# FTDI_FT230X_Example.net
KiCad netlist of a schematic drawn in EAGLE
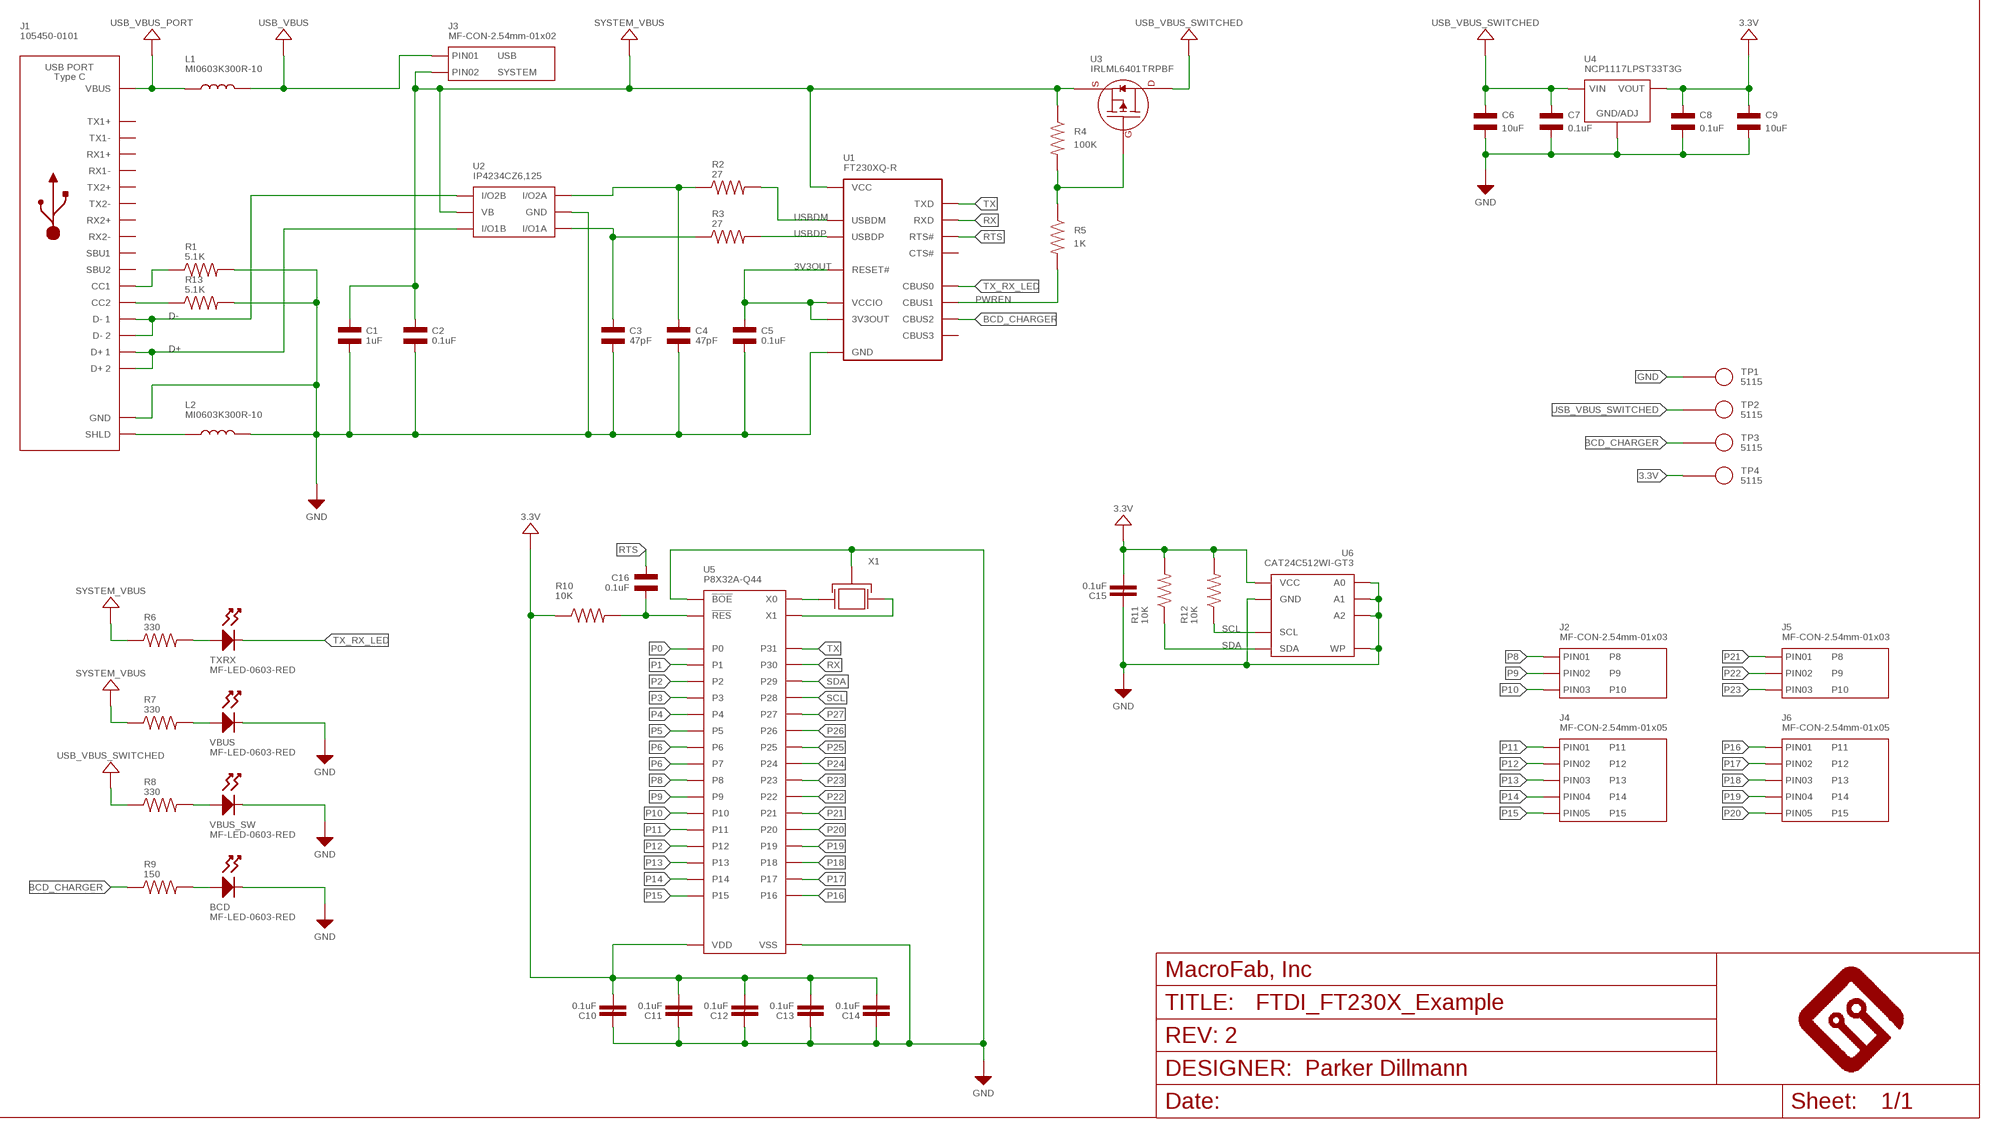
[diagram p0: schematic, sheet 1]

(export (version "E")
  (design (tool "Eeschema 10.0.6"))
  (components
    (comp (ref "BCD")
      (value "MF-LED-0603-RED")
      (footprint "eagle-import:LED0603")
      (fields (field (name "HOUSEPART") "YES"))
      (libsource (lib "eagle-import") (part "LED_SINGLE-0603-RED"))
    )
    (comp (ref "C1")
      (value "1uF")
      (footprint "eagle-import:C0603")
      (fields (field (name "MPN") "MF-CAP-0603-1uF"))
      (libsource (lib "eagle-import") (part "CAPACITOR_NP_0603"))
    )
    (comp (ref "C2")
      (value "0.1uF")
      (footprint "eagle-import:C0603")
      (fields (field (name "MPN") "MF-CAP-0603-0.1uF"))
      (libsource (lib "eagle-import") (part "CAPACITOR_NP_0603"))
    )
    (comp (ref "C3")
      (value "47pF")
      (footprint "eagle-import:C0603")
      (fields (field (name "MPN") "C0603C470J1GACTU"))
      (libsource (lib "eagle-import") (part "CAPACITOR_NP_0603"))
    )
    (comp (ref "C4")
      (value "47pF")
      (footprint "eagle-import:C0603")
      (fields (field (name "MPN") "C0603C470J1GACTU"))
      (libsource (lib "eagle-import") (part "CAPACITOR_NP_0603"))
    )
    (comp (ref "C5")
      (value "0.1uF")
      (footprint "eagle-import:C0603")
      (fields (field (name "MPN") "MF-CAP-0603-0.1uF"))
      (libsource (lib "eagle-import") (part "CAPACITOR_NP_0603"))
    )
    (comp (ref "C6")
      (value "10uF")
      (footprint "eagle-import:C1206")
      (fields (field (name "MPN") "MF-CAP-1206-10uF"))
      (libsource (lib "eagle-import") (part "CAPACITOR_NP_1206"))
    )
    (comp (ref "C7")
      (value "0.1uF")
      (footprint "eagle-import:C0603")
      (fields (field (name "MPN") "MF-CAP-0603-0.1uF"))
      (libsource (lib "eagle-import") (part "CAPACITOR_NP_0603"))
    )
    (comp (ref "C8")
      (value "0.1uF")
      (footprint "eagle-import:C0603")
      (fields (field (name "MPN") "MF-CAP-0603-0.1uF"))
      (libsource (lib "eagle-import") (part "CAPACITOR_NP_0603"))
    )
    (comp (ref "C9")
      (value "10uF")
      (footprint "eagle-import:C1206")
      (fields (field (name "MPN") "MF-CAP-1206-10uF"))
      (libsource (lib "eagle-import") (part "CAPACITOR_NP_1206"))
    )
    (comp (ref "C10")
      (value "0.1uF")
      (footprint "eagle-import:0603")
      (fields (field (name "MPN") "MF-CAP-0603-0.1uF"))
      (libsource (lib "eagle-import") (part "CAPACITOR_NON_POLAR_0603"))
    )
    (comp (ref "C11")
      (value "0.1uF")
      (footprint "eagle-import:0603")
      (fields (field (name "MPN") "MF-CAP-0603-0.1uF"))
      (libsource (lib "eagle-import") (part "CAPACITOR_NON_POLAR_0603"))
    )
    (comp (ref "C12")
      (value "0.1uF")
      (footprint "eagle-import:0603")
      (fields (field (name "MPN") "MF-CAP-0603-0.1uF"))
      (libsource (lib "eagle-import") (part "CAPACITOR_NON_POLAR_0603"))
    )
    (comp (ref "C13")
      (value "0.1uF")
      (footprint "eagle-import:0603")
      (fields (field (name "MPN") "MF-CAP-0603-0.1uF"))
      (libsource (lib "eagle-import") (part "CAPACITOR_NON_POLAR_0603"))
    )
    (comp (ref "C14")
      (value "0.1uF")
      (footprint "eagle-import:0603")
      (fields (field (name "MPN") "MF-CAP-0603-0.1uF"))
      (libsource (lib "eagle-import") (part "CAPACITOR_NON_POLAR_0603"))
    )
    (comp (ref "C15")
      (value "0.1uF")
      (footprint "eagle-import:0603")
      (fields (field (name "MPN") "MF-CAP-0603-0.1uF"))
      (libsource (lib "eagle-import") (part "CAPACITOR_NON_POLAR_0603"))
    )
    (comp (ref "C16")
      (value "0.1uF")
      (footprint "eagle-import:C0603")
      (fields (field (name "MPN") "MF-CAP-0603-0.1uF"))
      (libsource (lib "eagle-import") (part "CAPACITOR_NP_0603"))
    )
    (comp (ref "FRAME1")
      (value "MF_FRAMEDEFAULT")
      (footprint "eagle-import:MF_FRAME_DEFAULT")
      (fields
        (field (name "REVNUM") "REV: N/A")
        (field (name "DNAME") "N/A")
        (field (name "HOUSEPART") "0")
        (field (name "DNAME_1") "Parker Dillmann")
        (field (name "REVNUM_1") "REV: 2")
      )
      (libsource (lib "eagle-import") (part "MF_FRAMEDEFAULT"))
    )
    (comp (ref "J1")
      (value "105450-0101")
      (footprint "eagle-import:105450-0101")
      (fields (field (name "MPN") "105450-0101"))
      (libsource (lib "eagle-import") (part "USB_TYPE-C_105450-0101"))
    )
    (comp (ref "J2")
      (value "MF-CON-2.54mm-01x03")
      (footprint "eagle-import:PTH_2.54MM_01X03")
      (fields
        (field (name "HOUSEPART") "YES")
        (field (name "LABEL01") "P8")
        (field (name "LABEL02") "P9")
        (field (name "LABEL03") "P10")
        (field (name "POPULATE") "0")
      )
      (libsource (lib "eagle-import") (part "CON_01X03_PTH_2.54MM"))
    )
    (comp (ref "J3")
      (value "MF-CON-2.54mm-01x02")
      (footprint "eagle-import:PTH_2.54MM_01X02")
      (fields
        (field (name "HOUSEPART") "YES")
        (field (name "LABEL01") "USB")
        (field (name "LABEL02") "SYSTEM")
      )
      (libsource (lib "eagle-import") (part "CON_01X02_PTH_2.54MM"))
    )
    (comp (ref "J4")
      (value "MF-CON-2.54mm-01x05")
      (footprint "eagle-import:PTH_2.54MM_01X05")
      (fields
        (field (name "HOUSEPART") "YES")
        (field (name "LABEL01") "P11")
        (field (name "LABEL02") "P12")
        (field (name "LABEL03") "P13")
        (field (name "LABEL04") "P14")
        (field (name "LABEL05") "P15")
        (field (name "POPULATE") "0")
      )
      (libsource (lib "eagle-import") (part "CON_01X05_PTH_2.54MM"))
    )
    (comp (ref "J5")
      (value "MF-CON-2.54mm-01x03")
      (footprint "eagle-import:PTH_2.54MM_01X03")
      (fields
        (field (name "HOUSEPART") "YES")
        (field (name "LABEL01") "P8")
        (field (name "LABEL02") "P9")
        (field (name "LABEL03") "P10")
        (field (name "POPULATE") "0")
      )
      (libsource (lib "eagle-import") (part "CON_01X03_PTH_2.54MM"))
    )
    (comp (ref "J6")
      (value "MF-CON-2.54mm-01x05")
      (footprint "eagle-import:PTH_2.54MM_01X05")
      (fields
        (field (name "HOUSEPART") "YES")
        (field (name "LABEL01") "P11")
        (field (name "LABEL02") "P12")
        (field (name "LABEL03") "P13")
        (field (name "LABEL04") "P14")
        (field (name "LABEL05") "P15")
        (field (name "POPULATE") "0")
      )
      (libsource (lib "eagle-import") (part "CON_01X05_PTH_2.54MM"))
    )
    (comp (ref "L1")
      (value "MI0603K300R-10")
      (footprint "eagle-import:L0603")
      (fields (field (name "MPN") "MI0603K300R-10"))
      (libsource (lib "eagle-import") (part "INDUCTOR_0603"))
    )
    (comp (ref "L2")
      (value "MI0603K300R-10")
      (footprint "eagle-import:L0603")
      (fields (field (name "MPN") "MI0603K300R-10"))
      (libsource (lib "eagle-import") (part "INDUCTOR_0603"))
    )
    (comp (ref "R1")
      (value "5.1K")
      (footprint "eagle-import:R0603")
      (fields (field (name "MPN") "ERJ-3EKF5101V"))
      (libsource (lib "eagle-import") (part "RESISTOR_0603"))
    )
    (comp (ref "R2")
      (value "27")
      (footprint "eagle-import:R0603")
      (fields (field (name "MPN") "MF-RES-0603-27"))
      (libsource (lib "eagle-import") (part "RESISTOR_0603"))
    )
    (comp (ref "R3")
      (value "27")
      (footprint "eagle-import:R0603")
      (fields (field (name "MPN") "MF-RES-0603-27"))
      (libsource (lib "eagle-import") (part "RESISTOR_0603"))
    )
    (comp (ref "R4")
      (value "100K")
      (footprint "eagle-import:R0603")
      (fields (field (name "MPN") "MF-RES-0603-100K"))
      (libsource (lib "eagle-import") (part "RESISTOR_0603"))
    )
    (comp (ref "R5")
      (value "1K")
      (footprint "eagle-import:R0603")
      (fields (field (name "MPN") "MF-RES-0603-1K"))
      (libsource (lib "eagle-import") (part "RESISTOR_0603"))
    )
    (comp (ref "R6")
      (value "330")
      (footprint "eagle-import:R0603")
      (fields (field (name "MPN") "MF-RES-0603-330"))
      (libsource (lib "eagle-import") (part "RESISTOR_0603"))
    )
    (comp (ref "R7")
      (value "330")
      (footprint "eagle-import:R0603")
      (fields (field (name "MPN") "MF-RES-0603-330"))
      (libsource (lib "eagle-import") (part "RESISTOR_0603"))
    )
    (comp (ref "R8")
      (value "330")
      (footprint "eagle-import:R0603")
      (fields (field (name "MPN") "MF-RES-0603-330"))
      (libsource (lib "eagle-import") (part "RESISTOR_0603"))
    )
    (comp (ref "R9")
      (value "150")
      (footprint "eagle-import:R0603")
      (fields (field (name "MPN") "ERJ-3EKF1500V"))
      (libsource (lib "eagle-import") (part "RESISTOR_0603"))
    )
    (comp (ref "R10")
      (value "10K")
      (footprint "eagle-import:0603")
      (fields (field (name "MPN") "MF-RES-0603-10K"))
      (libsource (lib "eagle-import") (part "PP_Passives_RESISTOR_0603"))
    )
    (comp (ref "R11")
      (value "10K")
      (footprint "eagle-import:0603")
      (fields (field (name "MPN") "MF-RES-0603-10K"))
      (libsource (lib "eagle-import") (part "PP_Passives_RESISTOR_0603"))
    )
    (comp (ref "R12")
      (value "10K")
      (footprint "eagle-import:0603")
      (fields (field (name "MPN") "MF-RES-0603-10K"))
      (libsource (lib "eagle-import") (part "PP_Passives_RESISTOR_0603"))
    )
    (comp (ref "R13")
      (value "5.1K")
      (footprint "eagle-import:R0603")
      (fields (field (name "MPN") "ERJ-3EKF5101V"))
      (libsource (lib "eagle-import") (part "RESISTOR_0603"))
    )
    (comp (ref "TP1")
      (value "5115")
      (footprint "eagle-import:KEYSTONE_5115-5119")
      (fields (field (name "MPN") "Keystone 5115"))
      (libsource (lib "eagle-import") (part "TEST_POINT_SINGLE_KEYSTONE_5115-5119"))
    )
    (comp (ref "TP2")
      (value "5115")
      (footprint "eagle-import:KEYSTONE_5115-5119")
      (fields (field (name "MPN") "Keystone 5115"))
      (libsource (lib "eagle-import") (part "TEST_POINT_SINGLE_KEYSTONE_5115-5119"))
    )
    (comp (ref "TP3")
      (value "5115")
      (footprint "eagle-import:KEYSTONE_5115-5119")
      (fields (field (name "MPN") "Keystone 5115"))
      (libsource (lib "eagle-import") (part "TEST_POINT_SINGLE_KEYSTONE_5115-5119"))
    )
    (comp (ref "TP4")
      (value "5115")
      (footprint "eagle-import:KEYSTONE_5115-5119")
      (fields (field (name "MPN") "Keystone 5115"))
      (libsource (lib "eagle-import") (part "TEST_POINT_SINGLE_KEYSTONE_5115-5119"))
    )
    (comp (ref "TXRX")
      (value "MF-LED-0603-RED")
      (footprint "eagle-import:LED0603")
      (fields (field (name "HOUSEPART") "YES"))
      (libsource (lib "eagle-import") (part "LED_SINGLE-0603-RED"))
    )
    (comp (ref "U1")
      (value "FT230XQ-R")
      (footprint "eagle-import:FT230X_QFN-16")
      (libsource (lib "eagle-import") (part "FT230XQ"))
    )
    (comp (ref "U2")
      (value "IP4234CZ6,125")
      (footprint "eagle-import:IP4234CZ6_SOT-457-6")
      (libsource (lib "eagle-import") (part "IP4234CZ6"))
    )
    (comp (ref "U3")
      (value "IRLML6401TRPBF")
      (footprint "eagle-import:SOT-23-3")
      (libsource (lib "eagle-import") (part "MOSFET_P-CHANNEL_SINGLE_SOT-23"))
    )
    (comp (ref "U4")
      (value "NCP1117LPST33T3G")
      (footprint "eagle-import:SOT-223-3")
      (fields (field (name "HOUSEPART") "NO"))
      (libsource (lib "eagle-import") (part "NCP1117LPST33T3G"))
    )
    (comp (ref "U5")
      (value "P8X32A-Q44")
      (footprint "eagle-import:P8X32A_LQFP-44")
      (libsource (lib "eagle-import") (part "P8X32A-Q44"))
    )
    (comp (ref "U6")
      (value "CAT24C512WI-GT3")
      (footprint "eagle-import:SOIC-8_W")
      (libsource (lib "eagle-import") (part "EEPROM_I2CSOIC-8_W"))
    )
    (comp (ref "VBUS")
      (value "MF-LED-0603-RED")
      (footprint "eagle-import:LED0603")
      (fields (field (name "HOUSEPART") "YES"))
      (libsource (lib "eagle-import") (part "LED_SINGLE-0603-RED"))
    )
    (comp (ref "VBUS_SW")
      (value "MF-LED-0603-RED")
      (footprint "eagle-import:LED0603")
      (fields (field (name "HOUSEPART") "YES"))
      (libsource (lib "eagle-import") (part "LED_SINGLE-0603-RED"))
    )
    (comp (ref "X1")
      (value "ABMM-6.000MHZ-B2-T")
      (footprint "eagle-import:7MMX5MM")
      (fields (field (name "HOUSEPART") "NO") (field (name "MPN") "ABMM-6.000MHZ-B2-T"))
      (libsource (lib "eagle-import") (part "CYRSTAL_GND_ABMM"))
    )
  )
  (nets
    (net (code "1") (name "/3V3OUT") (class "Default")
      (node (ref "C5") (pin "P$1") (pinfunction "P$1_P$1") (pintype "passive"))
      (node (ref "U1") (pin "1") (pinfunction "VCCIO_1") (pintype "bidirectional"))
      (node (ref "U1") (pin "8") (pinfunction "3V3OUT_8") (pintype "bidirectional"))
      (node (ref "U1") (pin "9") (pinfunction "RESET#_9") (pintype "bidirectional"))
    )
    (net (code "2") (name "/D+") (class "Default")
      (node (ref "J1") (pin "A6") (pinfunction "D+1_A6") (pintype "bidirectional"))
      (node (ref "J1") (pin "B6") (pinfunction "D+2_B6") (pintype "bidirectional"))
      (node (ref "U2") (pin "3") (pinfunction "I/O1B_3") (pintype "bidirectional"))
    )
    (net (code "3") (name "/D-") (class "Default")
      (node (ref "J1") (pin "A7") (pinfunction "D-1_A7") (pintype "bidirectional"))
      (node (ref "J1") (pin "B7") (pinfunction "D-2_B7") (pintype "bidirectional"))
      (node (ref "U2") (pin "4") (pinfunction "I/O2B_4") (pintype "bidirectional"))
    )
    (net (code "4") (name "/PWREN") (class "Default")
      (node (ref "R5") (pin "P$2") (pinfunction "P$2_P$2") (pintype "passive"))
      (node (ref "U1") (pin "11") (pinfunction "CBUS1_11") (pintype "bidirectional"))
    )
    (net (code "5") (name "/USBDM") (class "Default")
      (node (ref "R2") (pin "P$2") (pinfunction "P$2_P$2") (pintype "passive"))
      (node (ref "U1") (pin "7") (pinfunction "USBDM_7") (pintype "bidirectional"))
    )
    (net (code "6") (name "/USBDP") (class "Default")
      (node (ref "R3") (pin "P$2") (pinfunction "P$2_P$2") (pintype "passive"))
      (node (ref "U1") (pin "6") (pinfunction "USBDP_6") (pintype "bidirectional"))
    )
    (net (code "7") (name "3.3V") (class "Default")
      (node (ref "C10") (pin "2") (pinfunction "2_2") (pintype "passive"))
      (node (ref "C11") (pin "2") (pinfunction "2_2") (pintype "passive"))
      (node (ref "C12") (pin "2") (pinfunction "2_2") (pintype "passive"))
      (node (ref "C13") (pin "2") (pinfunction "2_2") (pintype "passive"))
      (node (ref "C14") (pin "2") (pinfunction "2_2") (pintype "passive"))
      (node (ref "C15") (pin "2") (pinfunction "2_2") (pintype "passive"))
      (node (ref "C8") (pin "P$1") (pinfunction "P$1_P$1") (pintype "passive"))
      (node (ref "C9") (pin "P$1") (pinfunction "P$1_P$1") (pintype "passive"))
      (node (ref "R10") (pin "1") (pinfunction "1_1") (pintype "passive"))
      (node (ref "R11") (pin "2") (pinfunction "2_2") (pintype "passive"))
      (node (ref "R12") (pin "2") (pinfunction "2_2") (pintype "passive"))
      (node (ref "TP4") (pin "P$1") (pinfunction "P$1_P$1") (pintype "bidirectional"))
      (node (ref "U4") (pin "P$1") (pinfunction "VOUT_P$1") (pintype "bidirectional"))
      (node (ref "U4") (pin "P$3") (pinfunction "VOUT_P$3") (pintype "bidirectional"))
      (node (ref "U5") (pin "18") (pinfunction "VDD_18") (pintype "bidirectional"))
      (node (ref "U5") (pin "30") (pinfunction "VDD_30") (pintype "bidirectional"))
      (node (ref "U5") (pin "40") (pinfunction "VDD_40") (pintype "bidirectional"))
      (node (ref "U5") (pin "8") (pinfunction "VDD_8") (pintype "bidirectional"))
      (node (ref "U6") (pin "8") (pinfunction "VCC_8") (pintype "bidirectional"))
    )
    (net (code "8") (name "BCD_CHARGER") (class "Default")
      (node (ref "R9") (pin "P$1") (pinfunction "P$1_P$1") (pintype "passive"))
      (node (ref "TP3") (pin "P$1") (pinfunction "P$1_P$1") (pintype "bidirectional"))
      (node (ref "U1") (pin "5") (pinfunction "CBUS2_5") (pintype "bidirectional"))
    )
    (net (code "9") (name "GND") (class "Default")
      (node (ref "BCD") (pin "CATHODE") (pinfunction "CATHODE_CATHODE") (pintype "power_in"))
      (node (ref "C1") (pin "P$2") (pinfunction "P$2_P$2") (pintype "passive"))
      (node (ref "C10") (pin "1") (pinfunction "1_1") (pintype "passive"))
      (node (ref "C11") (pin "1") (pinfunction "1_1") (pintype "passive"))
      (node (ref "C12") (pin "1") (pinfunction "1_1") (pintype "passive"))
      (node (ref "C13") (pin "1") (pinfunction "1_1") (pintype "passive"))
      (node (ref "C14") (pin "1") (pinfunction "1_1") (pintype "passive"))
      (node (ref "C15") (pin "1") (pinfunction "1_1") (pintype "passive"))
      (node (ref "C2") (pin "P$2") (pinfunction "P$2_P$2") (pintype "passive"))
      (node (ref "C3") (pin "P$2") (pinfunction "P$2_P$2") (pintype "passive"))
      (node (ref "C4") (pin "P$2") (pinfunction "P$2_P$2") (pintype "passive"))
      (node (ref "C5") (pin "P$2") (pinfunction "P$2_P$2") (pintype "passive"))
      (node (ref "C6") (pin "P$2") (pinfunction "P$2_P$2") (pintype "passive"))
      (node (ref "C7") (pin "P$2") (pinfunction "P$2_P$2") (pintype "passive"))
      (node (ref "C8") (pin "P$2") (pinfunction "P$2_P$2") (pintype "passive"))
      (node (ref "C9") (pin "P$2") (pinfunction "P$2_P$2") (pintype "passive"))
      (node (ref "J1") (pin "A1") (pinfunction "GND_A1") (pintype "bidirectional"))
      (node (ref "J1") (pin "A12") (pinfunction "GND_A12") (pintype "bidirectional"))
      (node (ref "J1") (pin "B1") (pinfunction "GND_B1") (pintype "bidirectional"))
      (node (ref "J1") (pin "B12") (pinfunction "GND_B12") (pintype "bidirectional"))
      (node (ref "L2") (pin "P$2") (pinfunction "P$2_P$2") (pintype "passive"))
      (node (ref "R1") (pin "P$2") (pinfunction "P$2_P$2") (pintype "passive"))
      (node (ref "R13") (pin "P$2") (pinfunction "P$2_P$2") (pintype "passive"))
      (node (ref "TP1") (pin "P$1") (pinfunction "P$1_P$1") (pintype "bidirectional"))
      (node (ref "U1") (pin "13") (pinfunction "GND_13") (pintype "bidirectional"))
      (node (ref "U1") (pin "3") (pinfunction "GND_3") (pintype "bidirectional"))
      (node (ref "U1") (pin "PAD") (pinfunction "GND_PAD") (pintype "bidirectional"))
      (node (ref "U2") (pin "2") (pinfunction "GND_2") (pintype "bidirectional"))
      (node (ref "U4") (pin "P$2") (pinfunction "GND/ADJ_P$2") (pintype "bidirectional"))
      (node (ref "U5") (pin "17") (pinfunction "VSS_17") (pintype "bidirectional"))
      (node (ref "U5") (pin "27") (pinfunction "VSS_27") (pintype "bidirectional"))
      (node (ref "U5") (pin "39") (pinfunction "VSS_39") (pintype "bidirectional"))
      (node (ref "U5") (pin "5") (pinfunction "VSS_5") (pintype "bidirectional"))
      (node (ref "U5") (pin "6") (pinfunction "~{BOE}_6") (pintype "bidirectional"))
      (node (ref "U6") (pin "1") (pinfunction "A0_1") (pintype "bidirectional"))
      (node (ref "U6") (pin "2") (pinfunction "A1_2") (pintype "bidirectional"))
      (node (ref "U6") (pin "3") (pinfunction "A2_3") (pintype "bidirectional"))
      (node (ref "U6") (pin "4") (pinfunction "GND_4") (pintype "bidirectional"))
      (node (ref "U6") (pin "7") (pinfunction "WP_7") (pintype "bidirectional"))
      (node (ref "VBUS") (pin "CATHODE") (pinfunction "CATHODE_CATHODE") (pintype "power_in"))
      (node (ref "VBUS_SW") (pin "CATHODE") (pinfunction "CATHODE_CATHODE") (pintype "power_in"))
      (node (ref "X1") (pin "P$2") (pinfunction "GND_P$2") (pintype "bidirectional"))
      (node (ref "X1") (pin "P$4") (pinfunction "GND_P$4") (pintype "bidirectional"))
    )
    (net (code "10") (name "Net-(BCD-PadANODE)") (class "Default")
      (node (ref "BCD") (pin "ANODE") (pinfunction "ANODE_ANODE") (pintype "power_in"))
      (node (ref "R9") (pin "P$2") (pinfunction "P$2_P$2") (pintype "passive"))
    )
    (net (code "11") (name "Net-(J1-CC1)") (class "Default")
      (node (ref "J1") (pin "A5") (pinfunction "CC1_A5") (pintype "bidirectional"))
      (node (ref "R1") (pin "P$1") (pinfunction "P$1_P$1") (pintype "passive"))
    )
    (net (code "12") (name "Net-(J1-CC2)") (class "Default")
      (node (ref "J1") (pin "B5") (pinfunction "CC2_B5") (pintype "bidirectional"))
      (node (ref "R13") (pin "P$1") (pinfunction "P$1_P$1") (pintype "passive"))
    )
    (net (code "13") (name "Net-(J1-SHLD-PadS_T1)") (class "Default")
      (node (ref "J1") (pin "S_T1") (pinfunction "SHLD_S_T1") (pintype "bidirectional"))
      (node (ref "J1") (pin "S_T2") (pinfunction "SHLD_S_T2") (pintype "bidirectional"))
      (node (ref "J1") (pin "S_T3") (pinfunction "SHLD_S_T3") (pintype "bidirectional"))
      (node (ref "J1") (pin "S_T4") (pinfunction "SHLD_S_T4") (pintype "bidirectional"))
      (node (ref "L2") (pin "P$1") (pinfunction "P$1_P$1") (pintype "passive"))
    )
    (net (code "14") (name "Net-(R6-PadP$2)") (class "Default")
      (node (ref "R6") (pin "P$2") (pinfunction "P$2_P$2") (pintype "passive"))
      (node (ref "TXRX") (pin "ANODE") (pinfunction "ANODE_ANODE") (pintype "power_in"))
    )
    (net (code "15") (name "Net-(R7-PadP$2)") (class "Default")
      (node (ref "R7") (pin "P$2") (pinfunction "P$2_P$2") (pintype "passive"))
      (node (ref "VBUS") (pin "ANODE") (pinfunction "ANODE_ANODE") (pintype "power_in"))
    )
    (net (code "16") (name "Net-(R8-PadP$2)") (class "Default")
      (node (ref "R8") (pin "P$2") (pinfunction "P$2_P$2") (pintype "passive"))
      (node (ref "VBUS_SW") (pin "ANODE") (pinfunction "ANODE_ANODE") (pintype "power_in"))
    )
    (net (code "17") (name "Net-(U2-I{slash}O1A)") (class "Default")
      (node (ref "C3") (pin "P$1") (pinfunction "P$1_P$1") (pintype "passive"))
      (node (ref "R3") (pin "P$1") (pinfunction "P$1_P$1") (pintype "passive"))
      (node (ref "U2") (pin "1") (pinfunction "I/O1A_1") (pintype "bidirectional"))
    )
    (net (code "18") (name "Net-(U2-I{slash}O2A)") (class "Default")
      (node (ref "C4") (pin "P$1") (pinfunction "P$1_P$1") (pintype "passive"))
      (node (ref "R2") (pin "P$1") (pinfunction "P$1_P$1") (pintype "passive"))
      (node (ref "U2") (pin "6") (pinfunction "I/O2A_6") (pintype "bidirectional"))
    )
    (net (code "19") (name "Net-(U3-GATE)") (class "Default")
      (node (ref "R4") (pin "P$2") (pinfunction "P$2_P$2") (pintype "passive"))
      (node (ref "R5") (pin "P$1") (pinfunction "P$1_P$1") (pintype "passive"))
      (node (ref "U3") (pin "1") (pinfunction "GATE_1") (pintype "bidirectional"))
    )
    (net (code "20") (name "Net-(U5-X0)") (class "Default")
      (node (ref "U5") (pin "29") (pinfunction "X0_29") (pintype "bidirectional"))
      (node (ref "X1") (pin "P$3") (pinfunction "X1_P$3") (pintype "bidirectional"))
    )
    (net (code "21") (name "Net-(U5-X1)") (class "Default")
      (node (ref "U5") (pin "28") (pinfunction "X1_28") (pintype "bidirectional"))
      (node (ref "X1") (pin "P$1") (pinfunction "X0_P$1") (pintype "bidirectional"))
    )
    (net (code "22") (name "Net-(U5-~{RES})") (class "Default")
      (node (ref "C16") (pin "P$2") (pinfunction "P$2_P$2") (pintype "passive"))
      (node (ref "R10") (pin "2") (pinfunction "2_2") (pintype "passive"))
      (node (ref "U5") (pin "7") (pinfunction "~{RES}_7") (pintype "bidirectional"))
    )
    (net (code "23") (name "P0") (class "Default")
      (node (ref "U5") (pin "41") (pinfunction "P0_41") (pintype "bidirectional"))
    )
    (net (code "24") (name "P1") (class "Default")
      (node (ref "U5") (pin "42") (pinfunction "P1_42") (pintype "bidirectional"))
    )
    (net (code "25") (name "P2") (class "Default")
      (node (ref "U5") (pin "43") (pinfunction "P2_43") (pintype "bidirectional"))
    )
    (net (code "26") (name "P3") (class "Default")
      (node (ref "U5") (pin "44") (pinfunction "P3_44") (pintype "bidirectional"))
    )
    (net (code "27") (name "P4") (class "Default")
      (node (ref "U5") (pin "1") (pinfunction "P4_1") (pintype "bidirectional"))
    )
    (net (code "28") (name "P5") (class "Default")
      (node (ref "U5") (pin "2") (pinfunction "P5_2") (pintype "bidirectional"))
    )
    (net (code "29") (name "P6") (class "Default")
      (node (ref "U5") (pin "3") (pinfunction "P6_3") (pintype "bidirectional"))
    )
    (net (code "30") (name "P8") (class "Default")
      (node (ref "J2") (pin "P$1") (pinfunction "PIN1_P$1") (pintype "bidirectional"))
      (node (ref "U5") (pin "9") (pinfunction "P8_9") (pintype "bidirectional"))
    )
    (net (code "31") (name "P9") (class "Default")
      (node (ref "J2") (pin "P$2") (pinfunction "PIN2_P$2") (pintype "bidirectional"))
      (node (ref "U5") (pin "10") (pinfunction "P9_10") (pintype "bidirectional"))
    )
    (net (code "32") (name "P10") (class "Default")
      (node (ref "J2") (pin "P$3") (pinfunction "PIN3_P$3") (pintype "bidirectional"))
      (node (ref "U5") (pin "11") (pinfunction "P10_11") (pintype "bidirectional"))
    )
    (net (code "33") (name "P11") (class "Default")
      (node (ref "J4") (pin "P$1") (pinfunction "PIN1_P$1") (pintype "bidirectional"))
      (node (ref "U5") (pin "12") (pinfunction "P11_12") (pintype "bidirectional"))
    )
    (net (code "34") (name "P12") (class "Default")
      (node (ref "J4") (pin "P$2") (pinfunction "PIN2_P$2") (pintype "bidirectional"))
      (node (ref "U5") (pin "13") (pinfunction "P12_13") (pintype "bidirectional"))
    )
    (net (code "35") (name "P13") (class "Default")
      (node (ref "J4") (pin "P$3") (pinfunction "PIN3_P$3") (pintype "bidirectional"))
      (node (ref "U5") (pin "14") (pinfunction "P13_14") (pintype "bidirectional"))
    )
    (net (code "36") (name "P14") (class "Default")
      (node (ref "J4") (pin "P$4") (pinfunction "PIN4_P$4") (pintype "bidirectional"))
      (node (ref "U5") (pin "15") (pinfunction "P14_15") (pintype "bidirectional"))
    )
    (net (code "37") (name "P15") (class "Default")
      (node (ref "J4") (pin "P$5") (pinfunction "PIN5_P$5") (pintype "bidirectional"))
      (node (ref "U5") (pin "16") (pinfunction "P15_16") (pintype "bidirectional"))
    )
    (net (code "38") (name "P16") (class "Default")
      (node (ref "J6") (pin "P$1") (pinfunction "PIN1_P$1") (pintype "bidirectional"))
      (node (ref "U5") (pin "19") (pinfunction "P16_19") (pintype "bidirectional"))
    )
    (net (code "39") (name "P17") (class "Default")
      (node (ref "J6") (pin "P$2") (pinfunction "PIN2_P$2") (pintype "bidirectional"))
      (node (ref "U5") (pin "20") (pinfunction "P17_20") (pintype "bidirectional"))
    )
    (net (code "40") (name "P18") (class "Default")
      (node (ref "J6") (pin "P$3") (pinfunction "PIN3_P$3") (pintype "bidirectional"))
      (node (ref "U5") (pin "21") (pinfunction "P18_21") (pintype "bidirectional"))
    )
    (net (code "41") (name "P19") (class "Default")
      (node (ref "J6") (pin "P$4") (pinfunction "PIN4_P$4") (pintype "bidirectional"))
      (node (ref "U5") (pin "22") (pinfunction "P19_22") (pintype "bidirectional"))
    )
    (net (code "42") (name "P20") (class "Default")
      (node (ref "J6") (pin "P$5") (pinfunction "PIN5_P$5") (pintype "bidirectional"))
      (node (ref "U5") (pin "23") (pinfunction "P20_23") (pintype "bidirectional"))
    )
    (net (code "43") (name "P21") (class "Default")
      (node (ref "J5") (pin "P$1") (pinfunction "PIN1_P$1") (pintype "bidirectional"))
      (node (ref "U5") (pin "24") (pinfunction "P21_24") (pintype "bidirectional"))
    )
    (net (code "44") (name "P22") (class "Default")
      (node (ref "J5") (pin "P$2") (pinfunction "PIN2_P$2") (pintype "bidirectional"))
      (node (ref "U5") (pin "25") (pinfunction "P22_25") (pintype "bidirectional"))
    )
    (net (code "45") (name "P23") (class "Default")
      (node (ref "J5") (pin "P$3") (pinfunction "PIN3_P$3") (pintype "bidirectional"))
      (node (ref "U5") (pin "26") (pinfunction "P23_26") (pintype "bidirectional"))
    )
    (net (code "46") (name "P24") (class "Default")
      (node (ref "U5") (pin "31") (pinfunction "P24_31") (pintype "bidirectional"))
    )
    (net (code "47") (name "P25") (class "Default")
      (node (ref "U5") (pin "32") (pinfunction "P25_32") (pintype "bidirectional"))
    )
    (net (code "48") (name "P26") (class "Default")
      (node (ref "U5") (pin "33") (pinfunction "P26_33") (pintype "bidirectional"))
    )
    (net (code "49") (name "P27") (class "Default")
      (node (ref "U5") (pin "34") (pinfunction "P27_34") (pintype "bidirectional"))
    )
    (net (code "50") (name "RTS") (class "Default")
      (node (ref "C16") (pin "P$1") (pinfunction "P$1_P$1") (pintype "passive"))
      (node (ref "U1") (pin "16") (pinfunction "RTS#_16") (pintype "bidirectional"))
    )
    (net (code "51") (name "RX") (class "Default")
      (node (ref "U1") (pin "2") (pinfunction "RXD_2") (pintype "bidirectional"))
      (node (ref "U5") (pin "37") (pinfunction "P30_37") (pintype "bidirectional"))
    )
    (net (code "52") (name "SCL") (class "Default")
      (node (ref "R12") (pin "1") (pinfunction "1_1") (pintype "passive"))
      (node (ref "U5") (pin "35") (pinfunction "P28_35") (pintype "bidirectional"))
      (node (ref "U6") (pin "6") (pinfunction "SCL_6") (pintype "bidirectional"))
    )
    (net (code "53") (name "SDA") (class "Default")
      (node (ref "R11") (pin "1") (pinfunction "1_1") (pintype "passive"))
      (node (ref "U5") (pin "36") (pinfunction "P29_36") (pintype "bidirectional"))
      (node (ref "U6") (pin "5") (pinfunction "SDA_5") (pintype "bidirectional"))
    )
    (net (code "54") (name "SYSTEM_VBUS") (class "Default")
      (node (ref "C1") (pin "P$1") (pinfunction "P$1_P$1") (pintype "passive"))
      (node (ref "C2") (pin "P$1") (pinfunction "P$1_P$1") (pintype "passive"))
      (node (ref "J3") (pin "P$2") (pinfunction "PIN2_P$2") (pintype "bidirectional"))
      (node (ref "R4") (pin "P$1") (pinfunction "P$1_P$1") (pintype "passive"))
      (node (ref "R6") (pin "P$1") (pinfunction "P$1_P$1") (pintype "passive"))
      (node (ref "R7") (pin "P$1") (pinfunction "P$1_P$1") (pintype "passive"))
      (node (ref "U1") (pin "10") (pinfunction "VCC_10") (pintype "bidirectional"))
      (node (ref "U2") (pin "5") (pinfunction "VB_5") (pintype "bidirectional"))
      (node (ref "U3") (pin "2") (pinfunction "SOURCE_2") (pintype "bidirectional"))
    )
    (net (code "55") (name "TX") (class "Default")
      (node (ref "U1") (pin "15") (pinfunction "TXD_15") (pintype "bidirectional"))
      (node (ref "U5") (pin "38") (pinfunction "P31_38") (pintype "bidirectional"))
    )
    (net (code "56") (name "TX_RX_LED") (class "Default")
      (node (ref "TXRX") (pin "CATHODE") (pinfunction "CATHODE_CATHODE") (pintype "power_in"))
      (node (ref "U1") (pin "12") (pinfunction "CBUS0_12") (pintype "bidirectional"))
    )
    (net (code "57") (name "USB_VBUS") (class "Default")
      (node (ref "J3") (pin "P$1") (pinfunction "PIN1_P$1") (pintype "bidirectional"))
      (node (ref "L1") (pin "P$2") (pinfunction "P$2_P$2") (pintype "passive"))
    )
    (net (code "58") (name "USB_VBUS_PORT") (class "Default")
      (node (ref "J1") (pin "A4") (pinfunction "VBUS_A4") (pintype "bidirectional"))
      (node (ref "J1") (pin "A9") (pinfunction "VBUS_A9") (pintype "bidirectional"))
      (node (ref "J1") (pin "B4") (pinfunction "VBUS_B4") (pintype "bidirectional"))
      (node (ref "J1") (pin "B9") (pinfunction "VBUS_B9") (pintype "bidirectional"))
      (node (ref "L1") (pin "P$1") (pinfunction "P$1_P$1") (pintype "passive"))
    )
    (net (code "59") (name "USB_VBUS_SWITCHED") (class "Default")
      (node (ref "C6") (pin "P$1") (pinfunction "P$1_P$1") (pintype "passive"))
      (node (ref "C7") (pin "P$1") (pinfunction "P$1_P$1") (pintype "passive"))
      (node (ref "R8") (pin "P$1") (pinfunction "P$1_P$1") (pintype "passive"))
      (node (ref "TP2") (pin "P$1") (pinfunction "P$1_P$1") (pintype "bidirectional"))
      (node (ref "U3") (pin "3") (pinfunction "DRAIN_3") (pintype "bidirectional"))
      (node (ref "U4") (pin "P$4") (pinfunction "VIN_P$4") (pintype "bidirectional"))
    )
    (net (code "60") (name "unconnected-(J1-RX1+-PadB11)") (class "Default")
      (node (ref "J1") (pin "B11") (pinfunction "RX1+_B11") (pintype "bidirectional"))
    )
    (net (code "61") (name "unconnected-(J1-RX1--PadB10)") (class "Default")
      (node (ref "J1") (pin "B10") (pinfunction "RX1-_B10") (pintype "bidirectional"))
    )
    (net (code "62") (name "unconnected-(J1-RX2+-PadA11)") (class "Default")
      (node (ref "J1") (pin "A11") (pinfunction "RX2+_A11") (pintype "bidirectional"))
    )
    (net (code "63") (name "unconnected-(J1-RX2--PadA10)") (class "Default")
      (node (ref "J1") (pin "A10") (pinfunction "RX2-_A10") (pintype "bidirectional"))
    )
    (net (code "64") (name "unconnected-(J1-SBU1-PadA8)") (class "Default")
      (node (ref "J1") (pin "A8") (pinfunction "SBU1_A8") (pintype "bidirectional"))
    )
    (net (code "65") (name "unconnected-(J1-SBU2-PadB8)") (class "Default")
      (node (ref "J1") (pin "B8") (pinfunction "SBU2_B8") (pintype "bidirectional"))
    )
    (net (code "66") (name "unconnected-(J1-TX1+-PadA2)") (class "Default")
      (node (ref "J1") (pin "A2") (pinfunction "TX1+_A2") (pintype "bidirectional"))
    )
    (net (code "67") (name "unconnected-(J1-TX1--PadA3)") (class "Default")
      (node (ref "J1") (pin "A3") (pinfunction "TX1-_A3") (pintype "bidirectional"))
    )
    (net (code "68") (name "unconnected-(J1-TX2+-PadB2)") (class "Default")
      (node (ref "J1") (pin "B2") (pinfunction "TX2+_B2") (pintype "bidirectional"))
    )
    (net (code "69") (name "unconnected-(J1-TX2--PadB3)") (class "Default")
      (node (ref "J1") (pin "B3") (pinfunction "TX2-_B3") (pintype "bidirectional"))
    )
    (net (code "70") (name "unconnected-(U1-CBUS3-Pad14)") (class "Default")
      (node (ref "U1") (pin "14") (pinfunction "CBUS3_14") (pintype "bidirectional"))
    )
    (net (code "71") (name "unconnected-(U1-CTS#-Pad4)") (class "Default")
      (node (ref "U1") (pin "4") (pinfunction "CTS#_4") (pintype "bidirectional"))
    )
    (net (code "72") (name "unconnected-(U5-P7-Pad4)") (class "Default")
      (node (ref "U5") (pin "4") (pinfunction "P7_4") (pintype "bidirectional"))
    )
  )
)
